# DevCard.net
KiCad netlist of a schematic drawn in Altium Designer
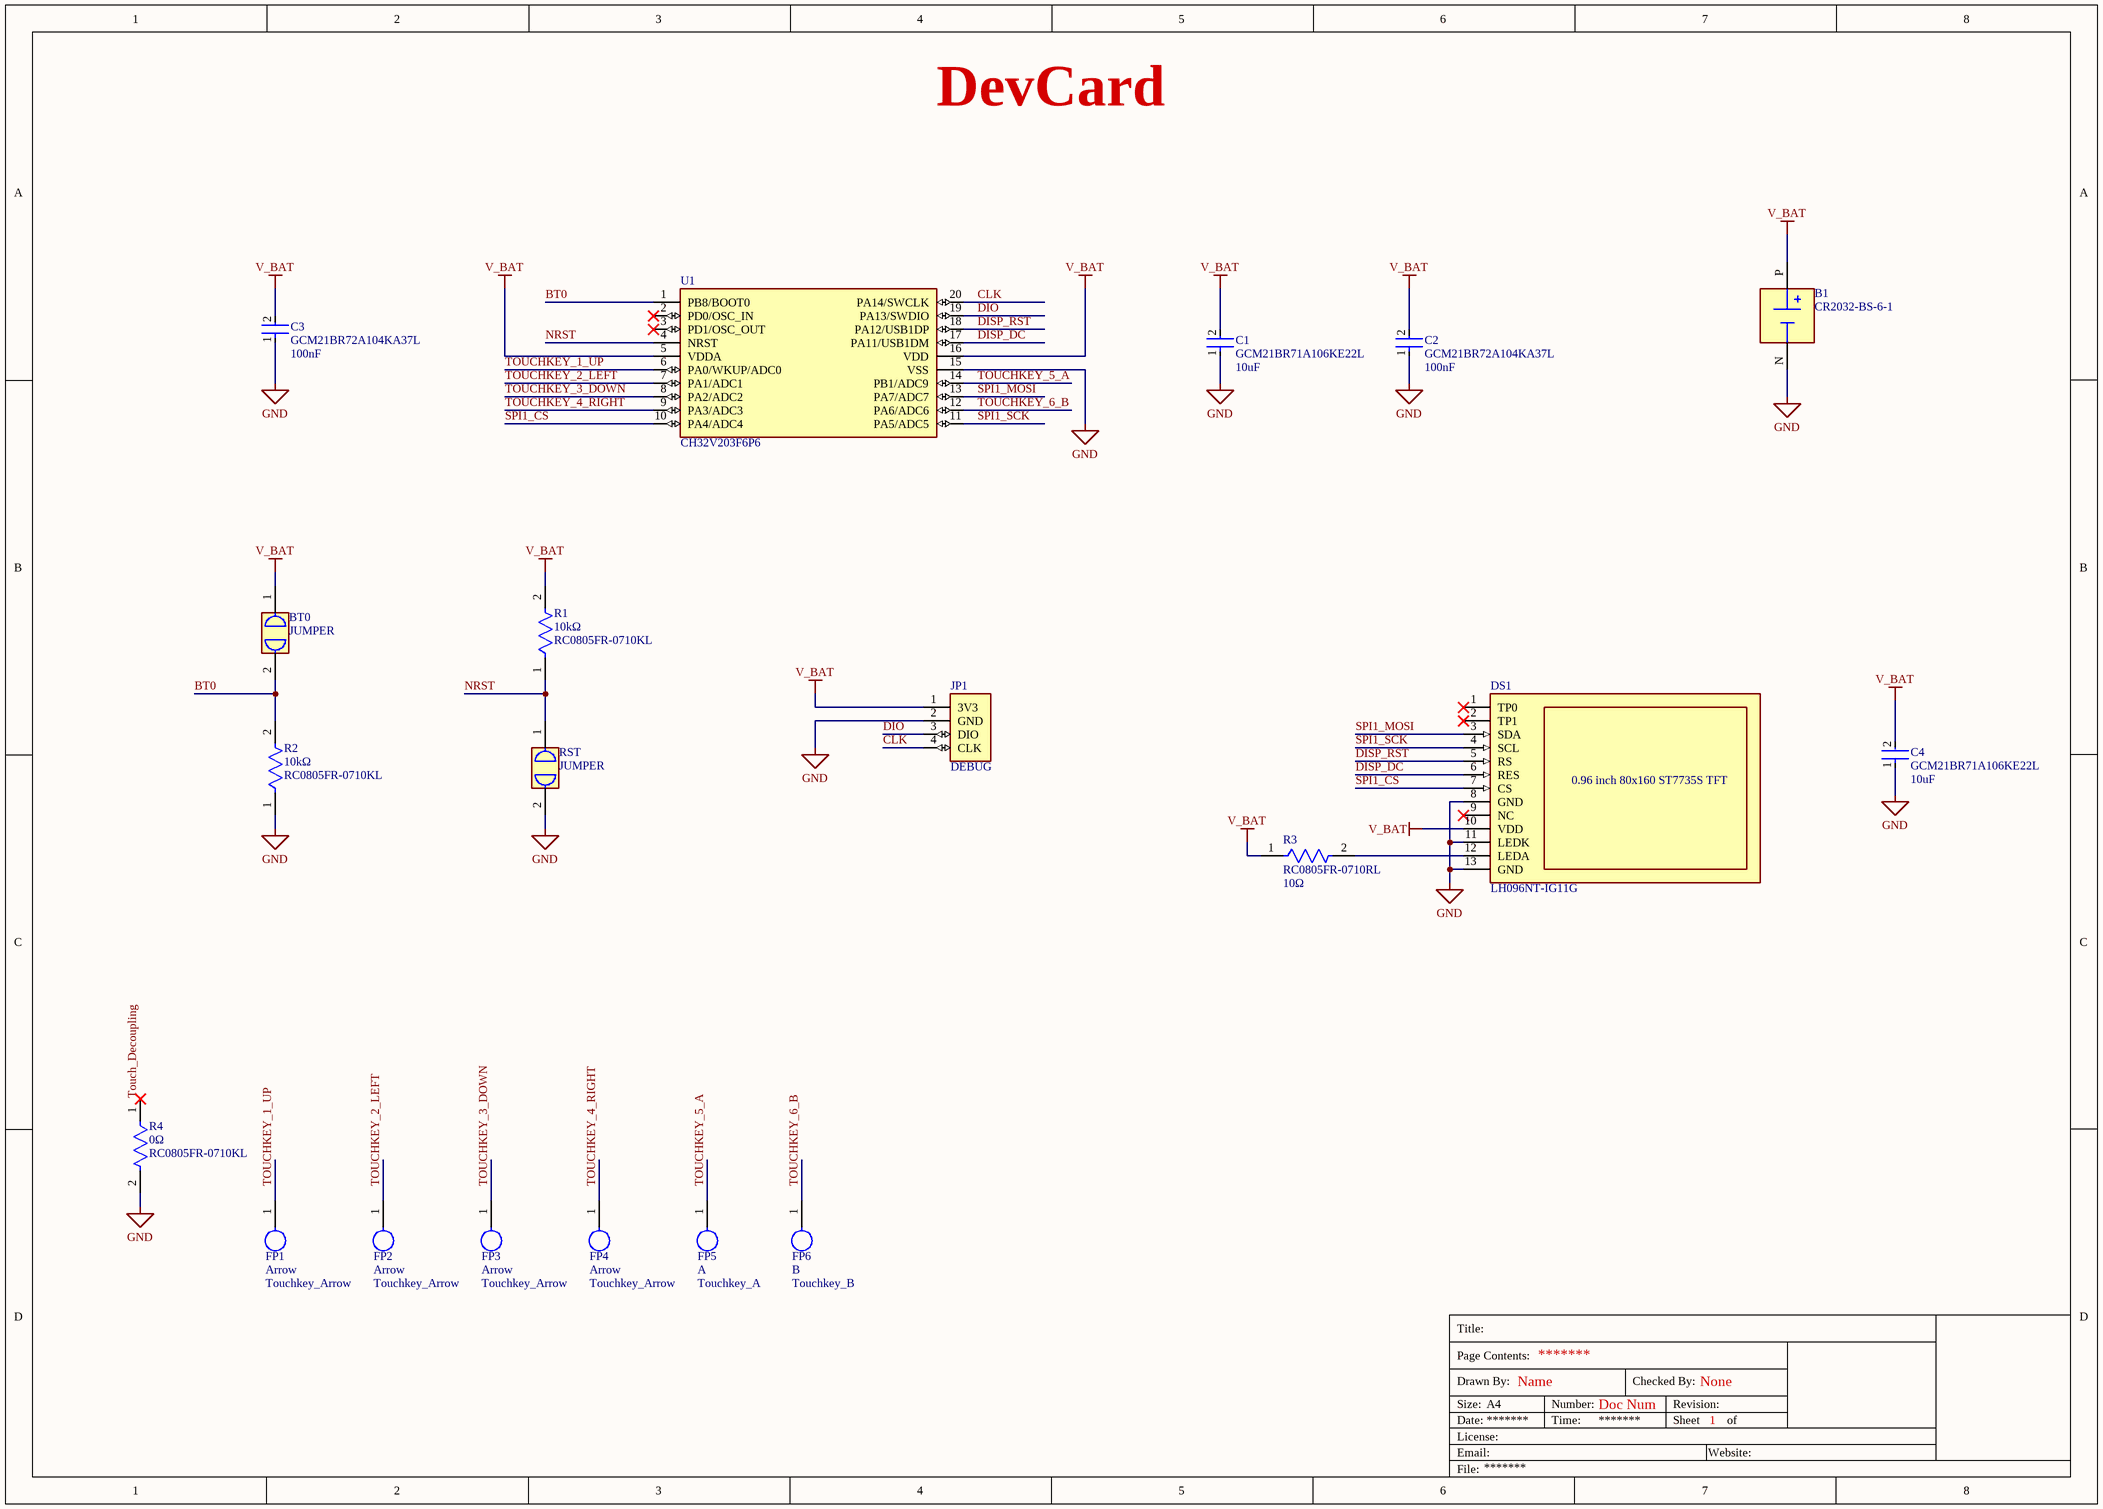
[diagram p0: DevCard.SchDoc]

(export (version "E")
  (design (tool "Eeschema 10.0.6"))
  (components
    (comp (ref "B1")
      (value "Battery")
      (footprint "BAT_CR2032-BS-6-1")
      (description "Battery holder CR2032 SMD")
      (fields
        (field (name "LCSC PART NUMBER") "C70377")
        (field (name "MANUFACTURER PART NUMBER") "CR2032-BS-6-1")
      )
      (libsource (lib "Library") (part "Battery"))
    )
    (comp (ref "BT0")
      (value "Jumper_BOOT")
      (footprint "JUMPER_BOOT")
      (description "Solder Jumper")
      (fields (field (name "MANUFACTURER PART NUMBER") "JUMPER"))
      (libsource (lib "Library") (part "Jumper_BOOT"))
    )
    (comp (ref "C1")
      (value "GCM21BR71A106KE22L")
      (footprint "C0805")
      (description "10uF X7R 0805 Multilayer Ceramic Capacitor")
      (fields
        (field (name "LCSC PART NUMBER") "C126586")
        (field (name "MANUFACTURER PART NUMBER") "GCM21BR71A106KE22L")
        (field (name "CAPACITANCE") "10uF")
      )
      (libsource (lib "Library") (part "GCM21BR71A106KE22L"))
    )
    (comp (ref "C2")
      (value "GCM21BR72A104KA37L")
      (footprint "C0805")
      (description "100nF X7R 0805 Multilayer Ceramic Capacitor")
      (fields
        (field (name "LCSC PART NUMBER") "C85866")
        (field (name "MANUFACTURER PART NUMBER") "GCM21BR72A104KA37L")
        (field (name "CAPACITANCE") "100nF")
      )
      (libsource (lib "Library") (part "GCM21BR72A104KA37L"))
    )
    (comp (ref "C3")
      (value "GCM21BR72A104KA37L")
      (footprint "C0805")
      (description "100nF X7R 0805 Multilayer Ceramic Capacitor")
      (fields
        (field (name "LCSC PART NUMBER") "C85866")
        (field (name "MANUFACTURER PART NUMBER") "GCM21BR72A104KA37L")
        (field (name "CAPACITANCE") "100nF")
      )
      (libsource (lib "Library") (part "GCM21BR72A104KA37L"))
    )
    (comp (ref "C4")
      (value "GCM21BR71A106KE22L")
      (footprint "C0805")
      (description "10uF X7R 0805 Multilayer Ceramic Capacitor")
      (fields
        (field (name "LCSC PART NUMBER") "C126586")
        (field (name "MANUFACTURER PART NUMBER") "GCM21BR71A106KE22L")
        (field (name "CAPACITANCE") "10uF")
      )
      (libsource (lib "Library") (part "GCM21BR71A106KE22L"))
    )
    (comp (ref "DS1")
      (value "Display")
      (footprint "0.96 - IPS LCD - No Glass - Flat")
      (description "0.96\" IPS Display 80x160 Pixel ST7735 Driver SPI")
      (fields (field (name "MANUFACTURER PART NUMBER") "LH096NT-IG11G"))
      (libsource (lib "Library") (part "Display"))
    )
    (comp (ref "FP1")
      (value "Arrow")
      (footprint "Touchkey_Arrow")
      (description "Touchkey Arrow")
      (fields (field (name "MANUFACTURER PART NUMBER") "Touchkey_Arrow"))
      (libsource (lib "Library") (part "Arrow"))
    )
    (comp (ref "FP2")
      (value "Arrow")
      (footprint "Touchkey_Arrow")
      (description "Touchkey Arrow")
      (fields (field (name "MANUFACTURER PART NUMBER") "Touchkey_Arrow"))
      (libsource (lib "Library") (part "Arrow"))
    )
    (comp (ref "FP3")
      (value "Arrow")
      (footprint "Touchkey_Arrow")
      (description "Touchkey Arrow")
      (fields (field (name "MANUFACTURER PART NUMBER") "Touchkey_Arrow"))
      (libsource (lib "Library") (part "Arrow"))
    )
    (comp (ref "FP4")
      (value "Arrow")
      (footprint "Touchkey_Arrow")
      (description "Touchkey Arrow")
      (fields (field (name "MANUFACTURER PART NUMBER") "Touchkey_Arrow"))
      (libsource (lib "Library") (part "Arrow"))
    )
    (comp (ref "FP5")
      (value "A")
      (footprint "Touchkey_A")
      (description "Touchkey A")
      (fields (field (name "MANUFACTURER PART NUMBER") "Touchkey_A"))
      (libsource (lib "Library") (part "A"))
    )
    (comp (ref "FP6")
      (value "B")
      (footprint "Touchkey_B")
      (description "Touchkey B")
      (fields (field (name "MANUFACTURER PART NUMBER") "Touchkey_B"))
      (libsource (lib "Library") (part "B"))
    )
    (comp (ref "GL1")
      (value "OPEN SOURCE HARDWARE")
      (footprint "OSH")
      (description "Open-source hardware image")
      (libsource (lib "Library") (part "OPEN SOURCE HARDWARE"))
    )
    (comp (ref "GL2")
      (value "LICENSE")
      (footprint "License")
      (description "Creative Commons")
      (libsource (lib "Library") (part "LICENSE"))
    )
    (comp (ref "GL3")
      (value "RV")
      (footprint "RV")
      (description "RISC-V Image")
      (libsource (lib "Library") (part "RV"))
    )
    (comp (ref "GL4")
      (value "Annoyedmilk")
      (footprint "Annoyedmilk")
      (description "Image")
      (libsource (lib "Library") (part "Annoyedmilk"))
    )
    (comp (ref "GL5")
      (value "myCard")
      (footprint "myCard")
      (description "Image")
      (libsource (lib "Library") (part "myCard"))
    )
    (comp (ref "JP1")
      (value "DEBUG")
      (footprint "DEBUG")
      (description "DEBUG Header")
      (fields (field (name "MANUFACTURER PART NUMBER") "DEBUG"))
      (libsource (lib "Library") (part "DEBUG"))
    )
    (comp (ref "R1")
      (value "RC0805FR-0710KL")
      (footprint "R0805")
      (description "10kΩ 0805 Chip Resistor")
      (fields
        (field (name "LCSC PART NUMBER") "C84376")
        (field (name "RESISTANCE") "10kΩ")
        (field (name "MANUFACTURER PART NUMBER") "RC0805FR-0710KL")
      )
      (libsource (lib "Library") (part "RC0805FR-0710KL"))
    )
    (comp (ref "R2")
      (value "RC0805FR-0710KL")
      (footprint "R0805")
      (description "10kΩ 0805 Chip Resistor")
      (fields
        (field (name "LCSC PART NUMBER") "C84376")
        (field (name "RESISTANCE") "10kΩ")
        (field (name "MANUFACTURER PART NUMBER") "RC0805FR-0710KL")
      )
      (libsource (lib "Library") (part "RC0805FR-0710KL"))
    )
    (comp (ref "R3")
      (value "RC0805FR-0710RL")
      (footprint "R0805")
      (description "10Ω 0805 Chip Resistor")
      (fields
        (field (name "LCSC PART NUMBER") "C96347")
        (field (name "MANUFACTURER PART NUMBER") "RC0805FR-0710RL")
        (field (name "RESISTANCE") "10Ω")
      )
      (libsource (lib "Library") (part "RC0805FR-0710RL"))
    )
    (comp (ref "R4")
      (value "RC0805FR-100RL")
      (footprint "R0805")
      (description "0Ω 0805 Chip Resistor")
      (fields
        (field (name "LCSC PART NUMBER") "C7336686")
        (field (name "RESISTANCE") "0Ω")
        (field (name "MANUFACTURER PART NUMBER") "RC0805FR-0710KL")
      )
      (libsource (lib "Library") (part "RC0805FR-100RL"))
    )
    (comp (ref "RST")
      (value "Jumper_RST")
      (footprint "JUMPER_RST")
      (description "Solder Jumper")
      (fields (field (name "MANUFACTURER PART NUMBER") "JUMPER"))
      (libsource (lib "Library") (part "Jumper_RST"))
    )
    (comp (ref "U1")
      (value "CH32V203F6P6")
      (footprint "SOP65P640X121-20N")
      (description "QingKe 32-bit RISC-V4B microcontroller up to 144MHz with 10KB SRAM, 32KB Flash (TSSOP20 Package)")
      (fields (field (name "MANUFACTURER PART NUMBER") "CH32V203F6P6"))
      (libsource (lib "Library") (part "CH32V203F6P6"))
    )
  )
  (nets
    (net (code "1") (name "/BT0") (class "Default")
      (node (ref "BT0") (pin "2") (pintype "power_in"))
      (node (ref "R2") (pin "2") (pinfunction "2_2") (pintype "passive"))
      (node (ref "U1") (pin "1") (pinfunction "PB8/BOOT0_1") (pintype "passive"))
    )
    (net (code "2") (name "/CLK") (class "Default")
      (node (ref "JP1") (pin "4") (pinfunction "CLK_4") (pintype "bidirectional"))
      (node (ref "U1") (pin "20") (pinfunction "PA14/SWCLK_20") (pintype "bidirectional"))
    )
    (net (code "3") (name "/DIO") (class "Default")
      (node (ref "JP1") (pin "3") (pinfunction "DIO_3") (pintype "bidirectional"))
      (node (ref "U1") (pin "19") (pinfunction "PA13/SWDIO_19") (pintype "bidirectional"))
    )
    (net (code "4") (name "/DISP_DC") (class "Default")
      (node (ref "DS1") (pin "6") (pinfunction "RES_6") (pintype "input"))
      (node (ref "U1") (pin "17") (pinfunction "PA11/USB1DM_17") (pintype "bidirectional"))
    )
    (net (code "5") (name "/DISP_RST") (class "Default")
      (node (ref "DS1") (pin "5") (pinfunction "RS_5") (pintype "input"))
      (node (ref "U1") (pin "18") (pinfunction "PA12/USB1DP_18") (pintype "bidirectional"))
    )
    (net (code "6") (name "/NRST") (class "Default")
      (node (ref "R1") (pin "1") (pinfunction "1_1") (pintype "passive"))
      (node (ref "RST") (pin "1") (pintype "power_in"))
      (node (ref "U1") (pin "4") (pinfunction "NRST_4") (pintype "passive"))
    )
    (net (code "7") (name "/SPI1_CS") (class "Default")
      (node (ref "DS1") (pin "7") (pinfunction "CS_7") (pintype "input"))
      (node (ref "U1") (pin "10") (pinfunction "PA4/ADC4_10") (pintype "bidirectional"))
    )
    (net (code "8") (name "/SPI1_MOSI") (class "Default")
      (node (ref "DS1") (pin "3") (pinfunction "SDA_3") (pintype "input"))
      (node (ref "U1") (pin "13") (pinfunction "PA7/ADC7_13") (pintype "bidirectional"))
    )
    (net (code "9") (name "/SPI1_SCK") (class "Default")
      (node (ref "DS1") (pin "4") (pinfunction "SCL_4") (pintype "input"))
      (node (ref "U1") (pin "11") (pinfunction "PA5/ADC5_11") (pintype "bidirectional"))
    )
    (net (code "10") (name "/TOUCHKEY_1_UP") (class "Default")
      (node (ref "FP1") (pin "1") (pintype "passive"))
      (node (ref "U1") (pin "6") (pinfunction "PA0/WKUP/ADC0_6") (pintype "bidirectional"))
    )
    (net (code "11") (name "/TOUCHKEY_2_LEFT") (class "Default")
      (node (ref "FP2") (pin "1") (pintype "passive"))
      (node (ref "U1") (pin "7") (pinfunction "PA1/ADC1_7") (pintype "bidirectional"))
    )
    (net (code "12") (name "/TOUCHKEY_3_DOWN") (class "Default")
      (node (ref "FP3") (pin "1") (pintype "passive"))
      (node (ref "U1") (pin "8") (pinfunction "PA2/ADC2_8") (pintype "bidirectional"))
    )
    (net (code "13") (name "/TOUCHKEY_4_RIGHT") (class "Default")
      (node (ref "FP4") (pin "1") (pintype "passive"))
      (node (ref "U1") (pin "9") (pinfunction "PA3/ADC3_9") (pintype "bidirectional"))
    )
    (net (code "14") (name "/TOUCHKEY_5_A") (class "Default")
      (node (ref "FP5") (pin "1") (pintype "passive"))
      (node (ref "U1") (pin "14") (pinfunction "PB1/ADC9_14") (pintype "bidirectional"))
    )
    (net (code "15") (name "/TOUCHKEY_6_B") (class "Default")
      (node (ref "FP6") (pin "1") (pintype "passive"))
      (node (ref "U1") (pin "12") (pinfunction "PA6/ADC6_12") (pintype "bidirectional"))
    )
    (net (code "16") (name "/Touch_Decoupling") (class "Default")
      (node (ref "R4") (pin "1") (pinfunction "1_1") (pintype "passive+no_connect"))
    )
    (net (code "17") (name "GND") (class "Default")
      (node (ref "B1") (pin "N") (pinfunction "NEG_N") (pintype "passive"))
      (node (ref "C1") (pin "1") (pinfunction "1_1") (pintype "passive"))
      (node (ref "C2") (pin "1") (pinfunction "1_1") (pintype "passive"))
      (node (ref "C3") (pin "1") (pinfunction "1_1") (pintype "passive"))
      (node (ref "C4") (pin "1") (pinfunction "1_1") (pintype "passive"))
      (node (ref "DS1") (pin "11") (pinfunction "LEDK_11") (pintype "passive"))
      (node (ref "DS1") (pin "13") (pinfunction "GND_13") (pintype "power_in"))
      (node (ref "DS1") (pin "8") (pinfunction "GND_8") (pintype "power_in"))
      (node (ref "JP1") (pin "2") (pinfunction "GND_2") (pintype "power_in"))
      (node (ref "R2") (pin "1") (pinfunction "1_1") (pintype "passive"))
      (node (ref "R4") (pin "2") (pinfunction "2_2") (pintype "passive"))
      (node (ref "RST") (pin "2") (pintype "power_in"))
      (node (ref "U1") (pin "15") (pinfunction "VSS_15") (pintype "power_in"))
    )
    (net (code "18") (name "Net-(DS1-LEDA)") (class "Default")
      (node (ref "DS1") (pin "12") (pinfunction "LEDA_12") (pintype "passive"))
      (node (ref "R3") (pin "2") (pinfunction "2_2") (pintype "passive"))
    )
    (net (code "19") (name "V_BAT") (class "Default")
      (node (ref "B1") (pin "P") (pinfunction "POS_P") (pintype "passive"))
      (node (ref "BT0") (pin "1") (pintype "power_in"))
      (node (ref "C1") (pin "2") (pinfunction "2_2") (pintype "passive"))
      (node (ref "C2") (pin "2") (pinfunction "2_2") (pintype "passive"))
      (node (ref "C3") (pin "2") (pinfunction "2_2") (pintype "passive"))
      (node (ref "C4") (pin "2") (pinfunction "2_2") (pintype "passive"))
      (node (ref "DS1") (pin "10") (pinfunction "VDD_10") (pintype "power_in"))
      (node (ref "JP1") (pin "1") (pinfunction "3V3_1") (pintype "power_in"))
      (node (ref "R1") (pin "2") (pinfunction "2_2") (pintype "passive"))
      (node (ref "R3") (pin "1") (pinfunction "1_1") (pintype "passive"))
      (node (ref "U1") (pin "16") (pinfunction "VDD_16") (pintype "power_in"))
      (node (ref "U1") (pin "5") (pinfunction "VDDA_5") (pintype "power_in"))
    )
    (net (code "20") (name "unconnected-(DS1-NC-Pad9)") (class "Default")
      (node (ref "DS1") (pin "9") (pinfunction "NC_9") (pintype "passive+no_connect"))
    )
    (net (code "21") (name "unconnected-(DS1-TP0-Pad1)") (class "Default")
      (node (ref "DS1") (pin "1") (pinfunction "TP0_1") (pintype "passive+no_connect"))
    )
    (net (code "22") (name "unconnected-(DS1-TP1-Pad2)") (class "Default")
      (node (ref "DS1") (pin "2") (pinfunction "TP1_2") (pintype "passive+no_connect"))
    )
    (net (code "23") (name "unconnected-(U1-PD0{slash}OSC_IN-Pad2)") (class "Default")
      (node (ref "U1") (pin "2") (pinfunction "PD0/OSC_IN_2") (pintype "bidirectional+no_connect"))
    )
    (net (code "24") (name "unconnected-(U1-PD1{slash}OSC_OUT-Pad3)") (class "Default")
      (node (ref "U1") (pin "3") (pinfunction "PD1/OSC_OUT_3") (pintype "bidirectional+no_connect"))
    )
  )
)
